# PROC051D_LP_Connector.net
KiCad netlist of a schematic drawn in Altium Designer
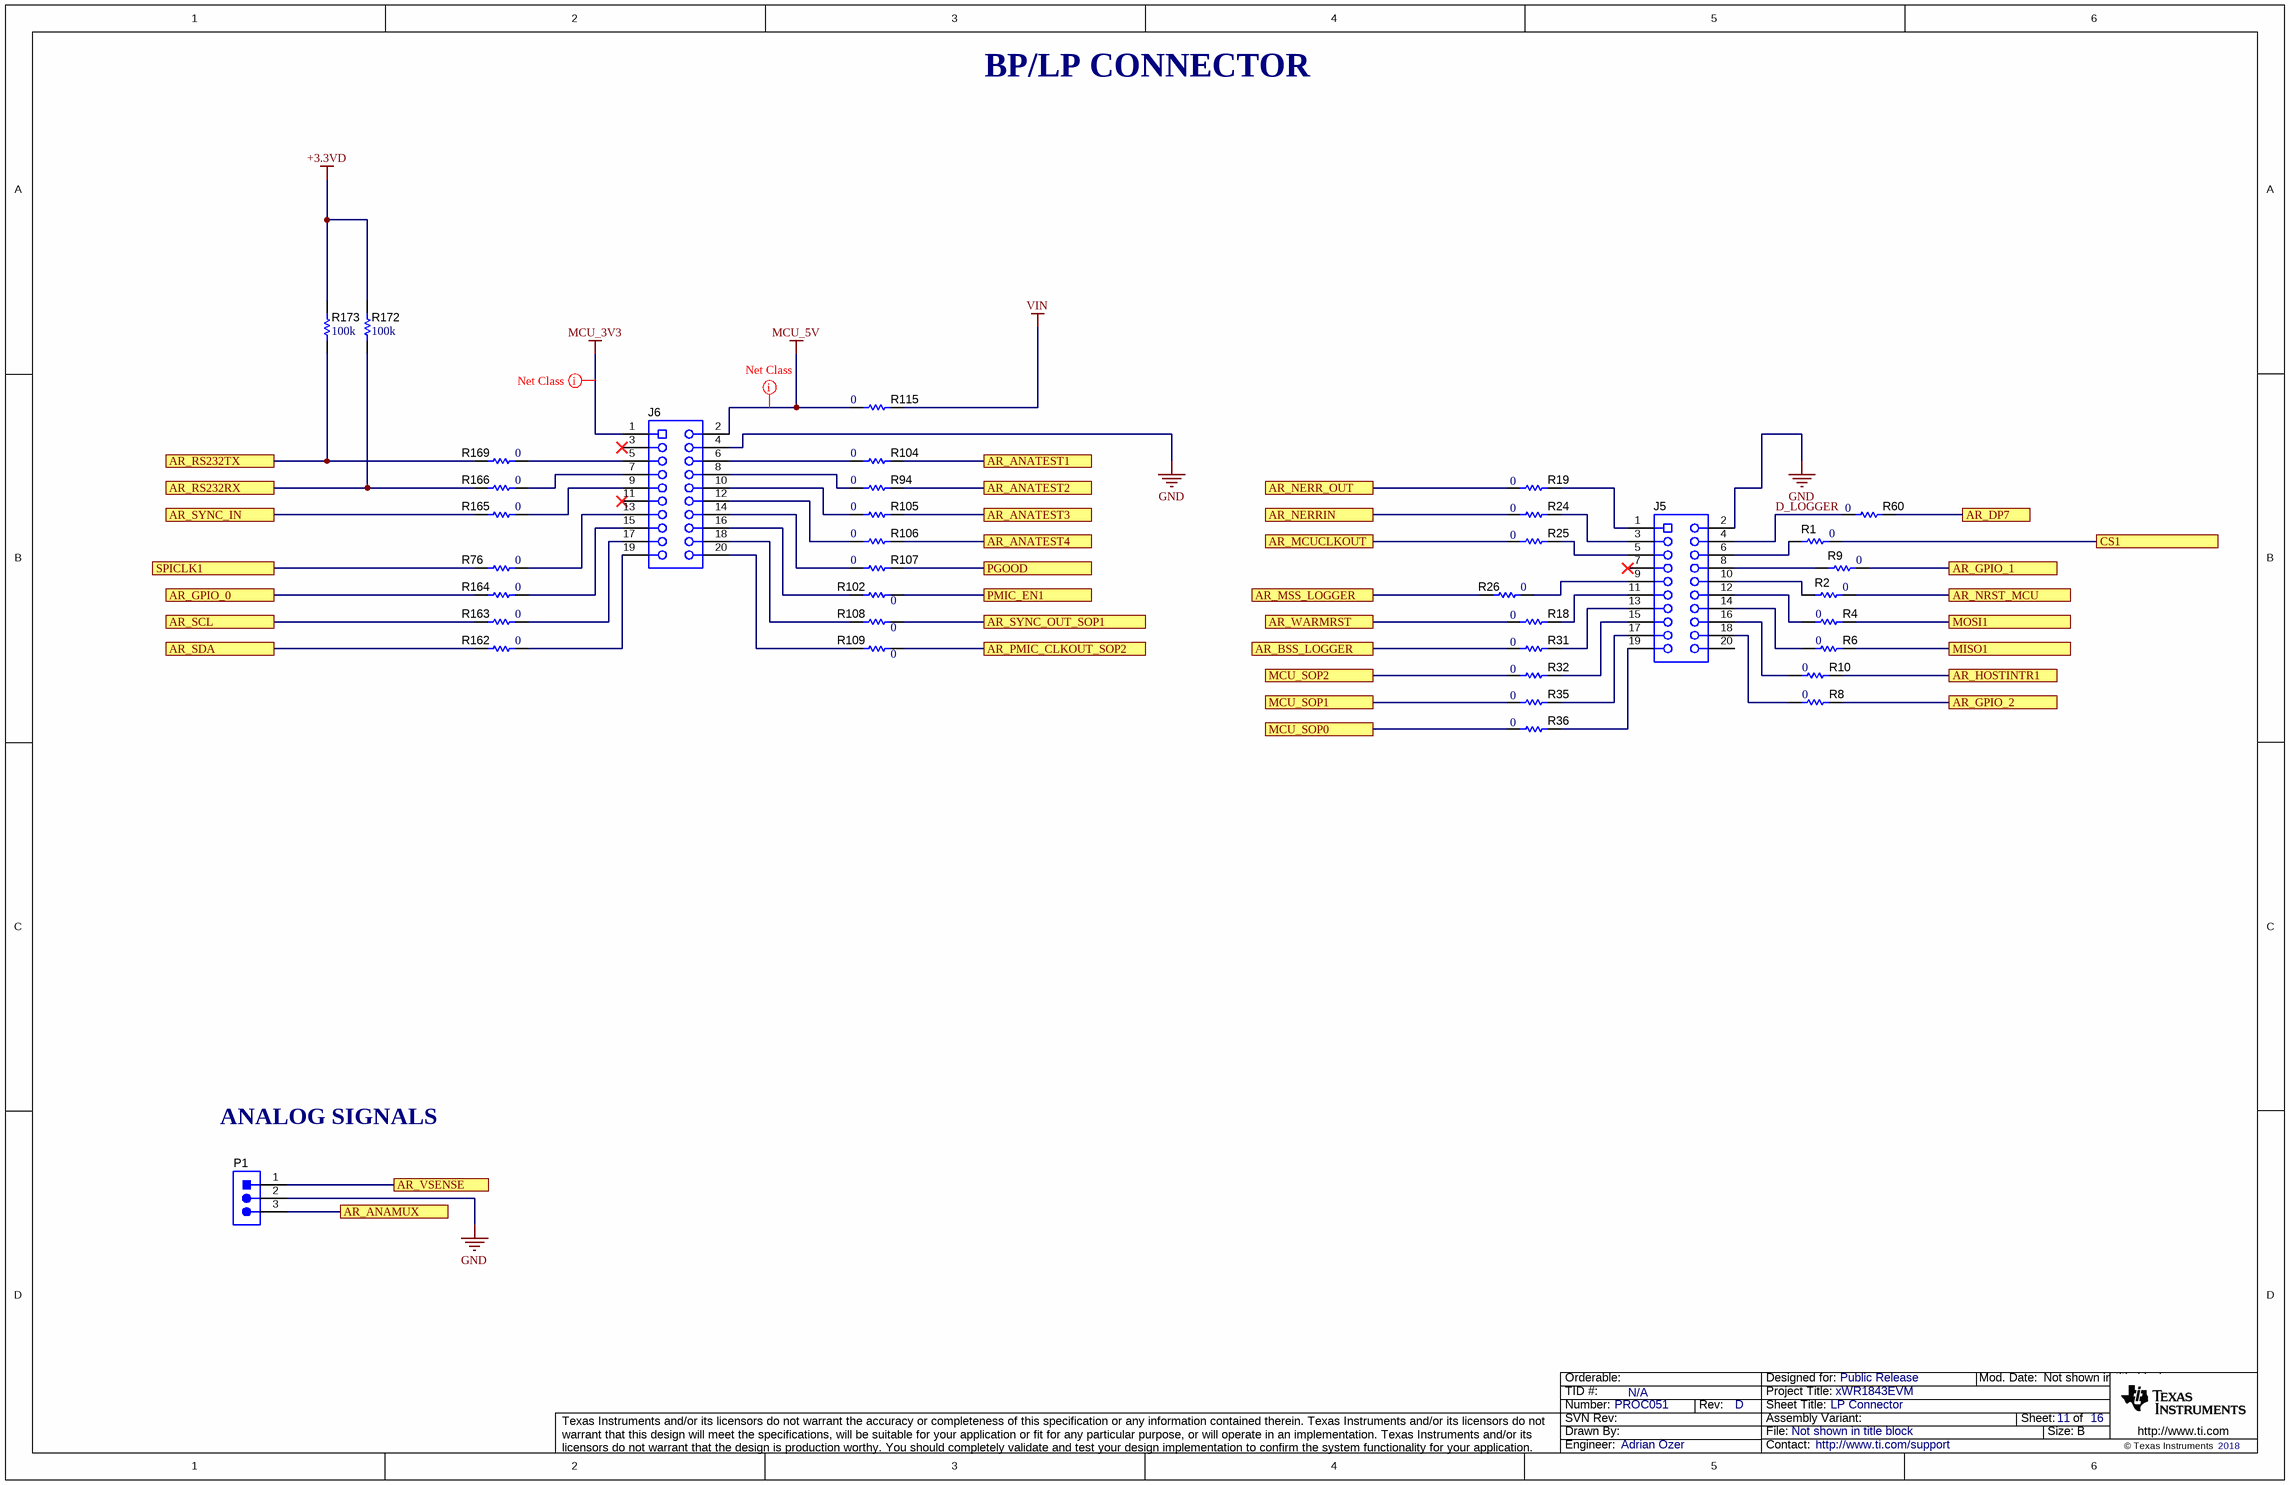
[diagram p0: PROC051D_LP Connector.SchDoc]

(export (version "E")
  (design (tool "Eeschema 10.0.6"))
  (components
    (comp (ref "J5")
      (value "SSM-110-S-DV")
      (footprint "Samtec_SSM-110-x-DV")
      (description "Receptacle, 2.54mm, 10x2, Gold with Tin tail, SMT")
      (fields (field (name "MANUFACTURER") "Samtec"))
      (libsource (lib "Altium Vault - TI") (part "CMP-0078182-1"))
    )
    (comp (ref "J6")
      (value "SSM-110-S-DV")
      (footprint "Samtec_SSM-110-x-DV")
      (description "Receptacle, 2.54mm, 10x2, Gold with Tin tail, SMT")
      (fields (field (name "MANUFACTURER") "Samtec"))
      (libsource (lib "Altium Vault - TI") (part "CMP-0078182-1"))
    )
    (comp (ref "P1")
      (value "TSW-103-07-T-S")
      (footprint "Samtec_TSW-103-07-T-S")
      (description "Header, 2.54 mm, 3x1, Tin, TH")
      (fields (field (name "MANUFACTURER") "Samtec"))
      (libsource (lib "Altium Vault - TI") (part "Header_3x1"))
    )
    (comp (ref "R1")
      (value "CRCW02010000Z0ED")
      (footprint "0201_Silk")
      (description "RES, 0, 5%, 0.05 W, 0201")
      (fields (field (name "MANUFACTURER") "Vishay-Dale") (field (name "VALUEDISPLAYED") "0"))
      (libsource (lib "Altium Vault - TI") (part "Resistor"))
    )
    (comp (ref "R2")
      (value "CRCW02010000Z0ED")
      (footprint "0201_Silk")
      (description "RES, 0, 5%, 0.05 W, 0201")
      (fields (field (name "MANUFACTURER") "Vishay-Dale") (field (name "VALUEDISPLAYED") "0"))
      (libsource (lib "Altium Vault - TI") (part "Resistor"))
    )
    (comp (ref "R4")
      (value "CRCW02010000Z0ED")
      (footprint "0201_Silk")
      (description "RES, 0, 5%, 0.05 W, 0201")
      (fields (field (name "MANUFACTURER") "Vishay-Dale") (field (name "VALUEDISPLAYED") "0"))
      (libsource (lib "Altium Vault - TI") (part "Resistor"))
    )
    (comp (ref "R6")
      (value "CRCW02010000Z0ED")
      (footprint "0201_Silk")
      (description "RES, 0, 5%, 0.05 W, 0201")
      (fields (field (name "MANUFACTURER") "Vishay-Dale") (field (name "VALUEDISPLAYED") "0"))
      (libsource (lib "Altium Vault - TI") (part "Resistor"))
    )
    (comp (ref "R8")
      (value "CRCW02010000Z0ED")
      (footprint "0201_Silk")
      (description "RES, 0, 5%, 0.05 W, 0201")
      (fields (field (name "MANUFACTURER") "Vishay-Dale") (field (name "VALUEDISPLAYED") "0"))
      (libsource (lib "Altium Vault - TI") (part "Resistor"))
    )
    (comp (ref "R9")
      (value "CRCW02010000Z0ED")
      (footprint "0201_Silk")
      (description "RES, 0, 5%, 0.05 W, 0201")
      (fields (field (name "MANUFACTURER") "Vishay-Dale") (field (name "VALUEDISPLAYED") "0"))
      (libsource (lib "Altium Vault - TI") (part "Resistor"))
    )
    (comp (ref "R10")
      (value "CRCW02010000Z0ED")
      (footprint "0201_Silk")
      (description "RES, 0, 5%, 0.05 W, 0201")
      (fields (field (name "MANUFACTURER") "Vishay-Dale") (field (name "VALUEDISPLAYED") "0"))
      (libsource (lib "Altium Vault - TI") (part "Resistor"))
    )
    (comp (ref "R18")
      (value "CRCW02010000Z0ED")
      (footprint "0201_Silk")
      (description "RES, 0, 5%, 0.05 W, 0201")
      (fields (field (name "MANUFACTURER") "Vishay-Dale") (field (name "VALUEDISPLAYED") "0"))
      (libsource (lib "Altium Vault - TI") (part "Resistor"))
    )
    (comp (ref "R19")
      (value "CRCW02010000Z0ED")
      (footprint "0201_Silk")
      (description "RES, 0, 5%, 0.05 W, 0201")
      (fields (field (name "MANUFACTURER") "Vishay-Dale") (field (name "VALUEDISPLAYED") "0"))
      (libsource (lib "Altium Vault - TI") (part "Resistor"))
    )
    (comp (ref "R24")
      (value "CRCW02010000Z0ED")
      (footprint "0201_Silk")
      (description "RES, 0, 5%, 0.05 W, 0201")
      (fields (field (name "MANUFACTURER") "Vishay-Dale") (field (name "VALUEDISPLAYED") "0"))
      (libsource (lib "Altium Vault - TI") (part "Resistor"))
    )
    (comp (ref "R25")
      (value "CRCW02010000Z0ED")
      (footprint "0201_Silk")
      (description "RES, 0, 5%, 0.05 W, 0201")
      (fields (field (name "MANUFACTURER") "Vishay-Dale") (field (name "VALUEDISPLAYED") "0"))
      (libsource (lib "Altium Vault - TI") (part "Resistor"))
    )
    (comp (ref "R26")
      (value "CRCW02010000Z0ED")
      (footprint "0201_Silk")
      (description "RES, 0, 5%, 0.05 W, 0201")
      (fields (field (name "MANUFACTURER") "Vishay-Dale") (field (name "VALUEDISPLAYED") "0"))
      (libsource (lib "Altium Vault - TI") (part "Resistor"))
    )
    (comp (ref "R31")
      (value "CRCW02010000Z0ED")
      (footprint "0201_Silk")
      (description "RES, 0, 5%, 0.05 W, 0201")
      (fields (field (name "MANUFACTURER") "Vishay-Dale") (field (name "VALUEDISPLAYED") "0"))
      (libsource (lib "Altium Vault - TI") (part "Resistor"))
    )
    (comp (ref "R32")
      (value "CRCW02010000Z0ED")
      (footprint "0201_Silk")
      (description "RES, 0, 5%, 0.05 W, 0201")
      (fields (field (name "MANUFACTURER") "Vishay-Dale") (field (name "VALUEDISPLAYED") "0"))
      (libsource (lib "Altium Vault - TI") (part "Resistor"))
    )
    (comp (ref "R35")
      (value "CRCW02010000Z0ED")
      (footprint "0201_Silk")
      (description "RES, 0, 5%, 0.05 W, 0201")
      (fields (field (name "MANUFACTURER") "Vishay-Dale") (field (name "VALUEDISPLAYED") "0"))
      (libsource (lib "Altium Vault - TI") (part "Resistor"))
    )
    (comp (ref "R36")
      (value "CRCW02010000Z0ED")
      (footprint "0201_Silk")
      (description "RES, 0, 5%, 0.05 W, 0201")
      (fields (field (name "MANUFACTURER") "Vishay-Dale") (field (name "VALUEDISPLAYED") "0"))
      (libsource (lib "Altium Vault - TI") (part "Resistor"))
    )
    (comp (ref "R60")
      (value "CRCW02010000Z0ED")
      (footprint "0201_Silk")
      (description "RES, 0, 5%, 0.05 W, 0201")
      (fields (field (name "MANUFACTURER") "Vishay-Dale") (field (name "VALUEDISPLAYED") "0"))
      (libsource (lib "Altium Vault - TI") (part "Resistor"))
    )
    (comp (ref "R76")
      (value "CRCW02010000Z0ED")
      (footprint "0201_Silk")
      (description "RES, 0, 5%, 0.05 W, 0201")
      (fields (field (name "MANUFACTURER") "Vishay-Dale") (field (name "VALUEDISPLAYED") "0"))
      (libsource (lib "Altium Vault - TI") (part "Resistor"))
    )
    (comp (ref "R94")
      (value "CRCW02010000Z0ED")
      (footprint "0201_Silk")
      (description "RES, 0, 5%, 0.05 W, 0201")
      (fields (field (name "MANUFACTURER") "Vishay-Dale") (field (name "VALUEDISPLAYED") "0"))
      (libsource (lib "Altium Vault - TI") (part "Resistor"))
    )
    (comp (ref "R102")
      (value "CRCW02010000Z0ED")
      (footprint "0201_Silk")
      (description "RES, 0, 5%, 0.05 W, 0201")
      (fields (field (name "MANUFACTURER") "Vishay-Dale") (field (name "VALUEDISPLAYED") "0"))
      (libsource (lib "Altium Vault - TI") (part "Resistor"))
    )
    (comp (ref "R104")
      (value "CRCW02010000Z0ED")
      (footprint "0201_Silk")
      (description "RES, 0, 5%, 0.05 W, 0201")
      (fields (field (name "MANUFACTURER") "Vishay-Dale") (field (name "VALUEDISPLAYED") "0"))
      (libsource (lib "Altium Vault - TI") (part "Resistor"))
    )
    (comp (ref "R105")
      (value "CRCW02010000Z0ED")
      (footprint "0201_Silk")
      (description "RES, 0, 5%, 0.05 W, 0201")
      (fields (field (name "MANUFACTURER") "Vishay-Dale") (field (name "VALUEDISPLAYED") "0"))
      (libsource (lib "Altium Vault - TI") (part "Resistor"))
    )
    (comp (ref "R106")
      (value "CRCW02010000Z0ED")
      (footprint "0201_Silk")
      (description "RES, 0, 5%, 0.05 W, 0201")
      (fields (field (name "MANUFACTURER") "Vishay-Dale") (field (name "VALUEDISPLAYED") "0"))
      (libsource (lib "Altium Vault - TI") (part "Resistor"))
    )
    (comp (ref "R107")
      (value "ERJ-2GE0R00X")
      (footprint "0402L")
      (description "RES, 0, 5%, 0.1 W, AEC-Q200 Grade 0, 0402")
      (fields (field (name "MANUFACTURER") "Panasonic") (field (name "VALUEDISPLAYED") "0"))
      (libsource (lib "Altium Vault - TI") (part "Resistor"))
    )
    (comp (ref "R108")
      (value "CRCW02010000Z0ED")
      (footprint "0201_Silk")
      (description "RES, 0, 5%, 0.05 W, 0201")
      (fields (field (name "MANUFACTURER") "Vishay-Dale") (field (name "VALUEDISPLAYED") "0"))
      (libsource (lib "Altium Vault - TI") (part "Resistor"))
    )
    (comp (ref "R109")
      (value "CRCW02010000Z0ED")
      (footprint "0201_Silk")
      (description "RES, 0, 5%, 0.05 W, 0201")
      (fields (field (name "MANUFACTURER") "Vishay-Dale") (field (name "VALUEDISPLAYED") "0"))
      (libsource (lib "Altium Vault - TI") (part "Resistor"))
    )
    (comp (ref "R115")
      (value "CRCW20100000Z0EF")
      (footprint "2010")
      (description "RES, 0, 5%, 0.75 W, AEC-Q200 Grade 0, 2010")
      (fields (field (name "MANUFACTURER") "Vishay-Dale") (field (name "VALUEDISPLAYED") "0"))
      (libsource (lib "Altium Vault - TI") (part "Resistor"))
    )
    (comp (ref "R162")
      (value "CRCW02010000Z0ED")
      (footprint "0201_Silk")
      (description "RES, 0, 5%, 0.05 W, 0201")
      (fields (field (name "MANUFACTURER") "Vishay-Dale") (field (name "VALUEDISPLAYED") "0"))
      (libsource (lib "Altium Vault - TI") (part "Resistor"))
    )
    (comp (ref "R163")
      (value "CRCW02010000Z0ED")
      (footprint "0201_Silk")
      (description "RES, 0, 5%, 0.05 W, 0201")
      (fields (field (name "MANUFACTURER") "Vishay-Dale") (field (name "VALUEDISPLAYED") "0"))
      (libsource (lib "Altium Vault - TI") (part "Resistor"))
    )
    (comp (ref "R164")
      (value "CRCW02010000Z0ED")
      (footprint "0201_Silk")
      (description "RES, 0, 5%, 0.05 W, 0201")
      (fields (field (name "MANUFACTURER") "Vishay-Dale") (field (name "VALUEDISPLAYED") "0"))
      (libsource (lib "Altium Vault - TI") (part "Resistor"))
    )
    (comp (ref "R165")
      (value "CRCW02010000Z0ED")
      (footprint "0201_Silk")
      (description "RES, 0, 5%, 0.05 W, 0201")
      (fields (field (name "MANUFACTURER") "Vishay-Dale") (field (name "VALUEDISPLAYED") "0"))
      (libsource (lib "Altium Vault - TI") (part "Resistor"))
    )
    (comp (ref "R166")
      (value "CRCW02010000Z0ED")
      (footprint "0201_Silk")
      (description "RES, 0, 5%, 0.05 W, 0201")
      (fields (field (name "MANUFACTURER") "Vishay-Dale") (field (name "VALUEDISPLAYED") "0"))
      (libsource (lib "Altium Vault - TI") (part "Resistor"))
    )
    (comp (ref "R169")
      (value "CRCW02010000Z0ED")
      (footprint "0201_Silk")
      (description "RES, 0, 5%, 0.05 W, 0201")
      (fields (field (name "MANUFACTURER") "Vishay-Dale") (field (name "VALUEDISPLAYED") "0"))
      (libsource (lib "Altium Vault - TI") (part "Resistor"))
    )
    (comp (ref "R172")
      (value "CRCW0402100KFKED")
      (footprint "0402L")
      (description "RES, 100 k, 1%, 0.063 W, AEC-Q200 Grade 0, 0402")
      (fields (field (name "MANUFACTURER") "Vishay-Dale") (field (name "VALUEDISPLAYED") "100k"))
      (libsource (lib "Altium Vault - TI") (part "Resistor"))
    )
    (comp (ref "R173")
      (value "CRCW0402100KFKED")
      (footprint "0402L")
      (description "RES, 100 k, 1%, 0.063 W, AEC-Q200 Grade 0, 0402")
      (fields (field (name "MANUFACTURER") "Vishay-Dale") (field (name "VALUEDISPLAYED") "100k"))
      (libsource (lib "Altium Vault - TI") (part "Resistor"))
    )
  )
  (nets
    (net (code "1") (name "+3.3VD") (class "Default")
      (node (ref "R172") (pin "2") (pinfunction "2_2") (pintype "passive"))
      (node (ref "R173") (pin "2") (pinfunction "2_2") (pintype "passive"))
    )
    (net (code "2") (name "/AR_ANAMUX") (class "Default")
      (node (ref "P1") (pin "3") (pinfunction "3_3") (pintype "passive"))
    )
    (net (code "3") (name "/AR_ANATEST1") (class "Default")
      (node (ref "R104") (pin "2") (pinfunction "2_2") (pintype "passive"))
    )
    (net (code "4") (name "/AR_ANATEST2") (class "Default")
      (node (ref "R94") (pin "2") (pinfunction "2_2") (pintype "passive"))
    )
    (net (code "5") (name "/AR_ANATEST3") (class "Default")
      (node (ref "R105") (pin "2") (pinfunction "2_2") (pintype "passive"))
    )
    (net (code "6") (name "/AR_ANATEST4") (class "Default")
      (node (ref "R106") (pin "2") (pinfunction "2_2") (pintype "passive"))
    )
    (net (code "7") (name "/AR_BSS_LOGGER") (class "Default")
      (node (ref "R31") (pin "1") (pinfunction "1_1") (pintype "passive"))
    )
    (net (code "8") (name "/AR_DP7") (class "Default")
      (node (ref "R60") (pin "2") (pinfunction "2_2") (pintype "passive"))
    )
    (net (code "9") (name "/AR_GPIO_0") (class "Default")
      (node (ref "R164") (pin "1") (pinfunction "1_1") (pintype "passive"))
    )
    (net (code "10") (name "/AR_GPIO_1") (class "Default")
      (node (ref "R9") (pin "2") (pinfunction "2_2") (pintype "passive"))
    )
    (net (code "11") (name "/AR_GPIO_2") (class "Default")
      (node (ref "R8") (pin "2") (pinfunction "2_2") (pintype "passive"))
    )
    (net (code "12") (name "/AR_HOSTINTR1") (class "Default")
      (node (ref "R10") (pin "2") (pinfunction "2_2") (pintype "passive"))
    )
    (net (code "13") (name "/AR_MCUCLKOUT") (class "Default")
      (node (ref "R25") (pin "1") (pinfunction "1_1") (pintype "passive"))
    )
    (net (code "14") (name "/AR_MSS_LOGGER") (class "Default")
      (node (ref "R26") (pin "1") (pinfunction "1_1") (pintype "passive"))
    )
    (net (code "15") (name "/AR_NERRIN") (class "Default")
      (node (ref "R24") (pin "1") (pinfunction "1_1") (pintype "passive"))
    )
    (net (code "16") (name "/AR_NERR_OUT") (class "Default")
      (node (ref "R19") (pin "1") (pinfunction "1_1") (pintype "passive"))
    )
    (net (code "17") (name "/AR_NRST_MCU") (class "Default")
      (node (ref "R2") (pin "2") (pinfunction "2_2") (pintype "passive"))
    )
    (net (code "18") (name "/AR_PMIC_CLKOUT_SOP2") (class "Default")
      (node (ref "R109") (pin "2") (pinfunction "2_2") (pintype "passive"))
    )
    (net (code "19") (name "/AR_RS232RX") (class "Default")
      (node (ref "R166") (pin "1") (pinfunction "1_1") (pintype "passive"))
      (node (ref "R172") (pin "1") (pinfunction "1_1") (pintype "passive"))
    )
    (net (code "20") (name "/AR_RS232TX") (class "Default")
      (node (ref "R169") (pin "1") (pinfunction "1_1") (pintype "passive"))
      (node (ref "R173") (pin "1") (pinfunction "1_1") (pintype "passive"))
    )
    (net (code "21") (name "/AR_SCL") (class "Default")
      (node (ref "R163") (pin "1") (pinfunction "1_1") (pintype "passive"))
    )
    (net (code "22") (name "/AR_SDA") (class "Default")
      (node (ref "R162") (pin "1") (pinfunction "1_1") (pintype "passive"))
    )
    (net (code "23") (name "/AR_SYNC_IN") (class "Default")
      (node (ref "R165") (pin "1") (pinfunction "1_1") (pintype "passive"))
    )
    (net (code "24") (name "/AR_SYNC_OUT_SOP1") (class "Default")
      (node (ref "R108") (pin "2") (pinfunction "2_2") (pintype "passive"))
    )
    (net (code "25") (name "/AR_VSENSE") (class "Default")
      (node (ref "P1") (pin "1") (pinfunction "1_1") (pintype "passive"))
    )
    (net (code "26") (name "/AR_WARMRST") (class "Default")
      (node (ref "R18") (pin "1") (pinfunction "1_1") (pintype "passive"))
    )
    (net (code "27") (name "/CS1") (class "Default")
      (node (ref "R1") (pin "2") (pinfunction "2_2") (pintype "passive"))
    )
    (net (code "28") (name "/D_LOGGER") (class "Default")
      (node (ref "J5") (pin "4") (pinfunction "4_4") (pintype "passive"))
      (node (ref "R60") (pin "1") (pinfunction "1_1") (pintype "passive"))
    )
    (net (code "29") (name "/MCU_SOP0") (class "Default")
      (node (ref "R36") (pin "1") (pinfunction "1_1") (pintype "passive"))
    )
    (net (code "30") (name "/MCU_SOP1") (class "Default")
      (node (ref "R35") (pin "1") (pinfunction "1_1") (pintype "passive"))
    )
    (net (code "31") (name "/MCU_SOP2") (class "Default")
      (node (ref "R32") (pin "1") (pinfunction "1_1") (pintype "passive"))
    )
    (net (code "32") (name "/MISO1") (class "Default")
      (node (ref "R6") (pin "2") (pinfunction "2_2") (pintype "passive"))
    )
    (net (code "33") (name "/MOSI1") (class "Default")
      (node (ref "R4") (pin "2") (pinfunction "2_2") (pintype "passive"))
    )
    (net (code "34") (name "/PGOOD") (class "Default")
      (node (ref "R107") (pin "2") (pinfunction "2_2") (pintype "passive"))
    )
    (net (code "35") (name "/PMIC_EN1") (class "Default")
      (node (ref "R102") (pin "2") (pinfunction "2_2") (pintype "passive"))
    )
    (net (code "36") (name "/SPICLK1") (class "Default")
      (node (ref "R76") (pin "1") (pinfunction "1_1") (pintype "passive"))
    )
    (net (code "37") (name "GND") (class "Default")
      (node (ref "J5") (pin "2") (pinfunction "2_2") (pintype "passive"))
      (node (ref "J6") (pin "4") (pinfunction "4_4") (pintype "passive"))
      (node (ref "P1") (pin "2") (pinfunction "2_2") (pintype "passive"))
    )
    (net (code "38") (name "MCU_3V3") (class "Default")
      (node (ref "J6") (pin "1") (pinfunction "1_1") (pintype "passive"))
    )
    (net (code "39") (name "MCU_5V") (class "Default")
      (node (ref "J6") (pin "2") (pinfunction "2_2") (pintype "passive"))
      (node (ref "R115") (pin "1") (pinfunction "1_1") (pintype "passive"))
    )
    (net (code "40") (name "Net-(J5-Pad1)") (class "Default")
      (node (ref "J5") (pin "1") (pinfunction "1_1") (pintype "passive"))
      (node (ref "R19") (pin "2") (pinfunction "2_2") (pintype "passive"))
    )
    (net (code "41") (name "Net-(J5-Pad3)") (class "Default")
      (node (ref "J5") (pin "3") (pinfunction "3_3") (pintype "passive"))
      (node (ref "R24") (pin "2") (pinfunction "2_2") (pintype "passive"))
    )
    (net (code "42") (name "Net-(J5-Pad5)") (class "Default")
      (node (ref "J5") (pin "5") (pinfunction "5_5") (pintype "passive"))
      (node (ref "R25") (pin "2") (pinfunction "2_2") (pintype "passive"))
    )
    (net (code "43") (name "Net-(J5-Pad6)") (class "Default")
      (node (ref "J5") (pin "6") (pinfunction "6_6") (pintype "passive"))
      (node (ref "R1") (pin "1") (pinfunction "1_1") (pintype "passive"))
    )
    (net (code "44") (name "Net-(J5-Pad8)") (class "Default")
      (node (ref "J5") (pin "8") (pinfunction "8_8") (pintype "passive"))
      (node (ref "R9") (pin "1") (pinfunction "1_1") (pintype "passive"))
    )
    (net (code "45") (name "Net-(J5-Pad9)") (class "Default")
      (node (ref "J5") (pin "9") (pinfunction "9_9") (pintype "passive"))
      (node (ref "R26") (pin "2") (pinfunction "2_2") (pintype "passive"))
    )
    (net (code "46") (name "Net-(J5-Pad10)") (class "Default")
      (node (ref "J5") (pin "10") (pinfunction "10_10") (pintype "passive"))
      (node (ref "R2") (pin "1") (pinfunction "1_1") (pintype "passive"))
    )
    (net (code "47") (name "Net-(J5-Pad11)") (class "Default")
      (node (ref "J5") (pin "11") (pinfunction "11_11") (pintype "passive"))
      (node (ref "R18") (pin "2") (pinfunction "2_2") (pintype "passive"))
    )
    (net (code "48") (name "Net-(J5-Pad12)") (class "Default")
      (node (ref "J5") (pin "12") (pinfunction "12_12") (pintype "passive"))
      (node (ref "R4") (pin "1") (pinfunction "1_1") (pintype "passive"))
    )
    (net (code "49") (name "Net-(J5-Pad13)") (class "Default")
      (node (ref "J5") (pin "13") (pinfunction "13_13") (pintype "passive"))
      (node (ref "R31") (pin "2") (pinfunction "2_2") (pintype "passive"))
    )
    (net (code "50") (name "Net-(J5-Pad14)") (class "Default")
      (node (ref "J5") (pin "14") (pinfunction "14_14") (pintype "passive"))
      (node (ref "R6") (pin "1") (pinfunction "1_1") (pintype "passive"))
    )
    (net (code "51") (name "Net-(J5-Pad15)") (class "Default")
      (node (ref "J5") (pin "15") (pinfunction "15_15") (pintype "passive"))
      (node (ref "R32") (pin "2") (pinfunction "2_2") (pintype "passive"))
    )
    (net (code "52") (name "Net-(J5-Pad16)") (class "Default")
      (node (ref "J5") (pin "16") (pinfunction "16_16") (pintype "passive"))
      (node (ref "R10") (pin "1") (pinfunction "1_1") (pintype "passive"))
    )
    (net (code "53") (name "Net-(J5-Pad17)") (class "Default")
      (node (ref "J5") (pin "17") (pinfunction "17_17") (pintype "passive"))
      (node (ref "R35") (pin "2") (pinfunction "2_2") (pintype "passive"))
    )
    (net (code "54") (name "Net-(J5-Pad18)") (class "Default")
      (node (ref "J5") (pin "18") (pinfunction "18_18") (pintype "passive"))
      (node (ref "R8") (pin "1") (pinfunction "1_1") (pintype "passive"))
    )
    (net (code "55") (name "Net-(J5-Pad19)") (class "Default")
      (node (ref "J5") (pin "19") (pinfunction "19_19") (pintype "passive"))
      (node (ref "R36") (pin "2") (pinfunction "2_2") (pintype "passive"))
    )
    (net (code "56") (name "Net-(J6-Pad5)") (class "Default")
      (node (ref "J6") (pin "5") (pinfunction "5_5") (pintype "passive"))
      (node (ref "R169") (pin "2") (pinfunction "2_2") (pintype "passive"))
    )
    (net (code "57") (name "Net-(J6-Pad6)") (class "Default")
      (node (ref "J6") (pin "6") (pinfunction "6_6") (pintype "passive"))
      (node (ref "R104") (pin "1") (pinfunction "1_1") (pintype "passive"))
    )
    (net (code "58") (name "Net-(J6-Pad7)") (class "Default")
      (node (ref "J6") (pin "7") (pinfunction "7_7") (pintype "passive"))
      (node (ref "R166") (pin "2") (pinfunction "2_2") (pintype "passive"))
    )
    (net (code "59") (name "Net-(J6-Pad8)") (class "Default")
      (node (ref "J6") (pin "8") (pinfunction "8_8") (pintype "passive"))
      (node (ref "R94") (pin "1") (pinfunction "1_1") (pintype "passive"))
    )
    (net (code "60") (name "Net-(J6-Pad9)") (class "Default")
      (node (ref "J6") (pin "9") (pinfunction "9_9") (pintype "passive"))
      (node (ref "R165") (pin "2") (pinfunction "2_2") (pintype "passive"))
    )
    (net (code "61") (name "Net-(J6-Pad10)") (class "Default")
      (node (ref "J6") (pin "10") (pinfunction "10_10") (pintype "passive"))
      (node (ref "R105") (pin "1") (pinfunction "1_1") (pintype "passive"))
    )
    (net (code "62") (name "Net-(J6-Pad12)") (class "Default")
      (node (ref "J6") (pin "12") (pinfunction "12_12") (pintype "passive"))
      (node (ref "R106") (pin "1") (pinfunction "1_1") (pintype "passive"))
    )
    (net (code "63") (name "Net-(J6-Pad13)") (class "Default")
      (node (ref "J6") (pin "13") (pinfunction "13_13") (pintype "passive"))
      (node (ref "R76") (pin "2") (pinfunction "2_2") (pintype "passive"))
    )
    (net (code "64") (name "Net-(J6-Pad14)") (class "Default")
      (node (ref "J6") (pin "14") (pinfunction "14_14") (pintype "passive"))
      (node (ref "R107") (pin "1") (pinfunction "1_1") (pintype "passive"))
    )
    (net (code "65") (name "Net-(J6-Pad15)") (class "Default")
      (node (ref "J6") (pin "15") (pinfunction "15_15") (pintype "passive"))
      (node (ref "R164") (pin "2") (pinfunction "2_2") (pintype "passive"))
    )
    (net (code "66") (name "Net-(J6-Pad16)") (class "Default")
      (node (ref "J6") (pin "16") (pinfunction "16_16") (pintype "passive"))
      (node (ref "R102") (pin "1") (pinfunction "1_1") (pintype "passive"))
    )
    (net (code "67") (name "Net-(J6-Pad17)") (class "Default")
      (node (ref "J6") (pin "17") (pinfunction "17_17") (pintype "passive"))
      (node (ref "R163") (pin "2") (pinfunction "2_2") (pintype "passive"))
    )
    (net (code "68") (name "Net-(J6-Pad18)") (class "Default")
      (node (ref "J6") (pin "18") (pinfunction "18_18") (pintype "passive"))
      (node (ref "R108") (pin "1") (pinfunction "1_1") (pintype "passive"))
    )
    (net (code "69") (name "Net-(J6-Pad19)") (class "Default")
      (node (ref "J6") (pin "19") (pinfunction "19_19") (pintype "passive"))
      (node (ref "R162") (pin "2") (pinfunction "2_2") (pintype "passive"))
    )
    (net (code "70") (name "Net-(J6-Pad20)") (class "Default")
      (node (ref "J6") (pin "20") (pinfunction "20_20") (pintype "passive"))
      (node (ref "R109") (pin "1") (pinfunction "1_1") (pintype "passive"))
    )
    (net (code "71") (name "VIN") (class "Default")
      (node (ref "R115") (pin "2") (pinfunction "2_2") (pintype "passive"))
    )
    (net (code "72") (name "unconnected-(J5-Pad7)") (class "Default")
      (node (ref "J5") (pin "7") (pinfunction "7_7") (pintype "passive+no_connect"))
    )
    (net (code "73") (name "unconnected-(J5-Pad20)") (class "Default")
      (node (ref "J5") (pin "20") (pinfunction "20_20") (pintype "passive"))
    )
    (net (code "74") (name "unconnected-(J6-Pad3)") (class "Default")
      (node (ref "J6") (pin "3") (pinfunction "3_3") (pintype "passive+no_connect"))
    )
    (net (code "75") (name "unconnected-(J6-Pad11)") (class "Default")
      (node (ref "J6") (pin "11") (pinfunction "11_11") (pintype "passive+no_connect"))
    )
  )
)
